# MARS_GPIO_MISC.net
KiCad netlist of a schematic drawn in Altium Designer
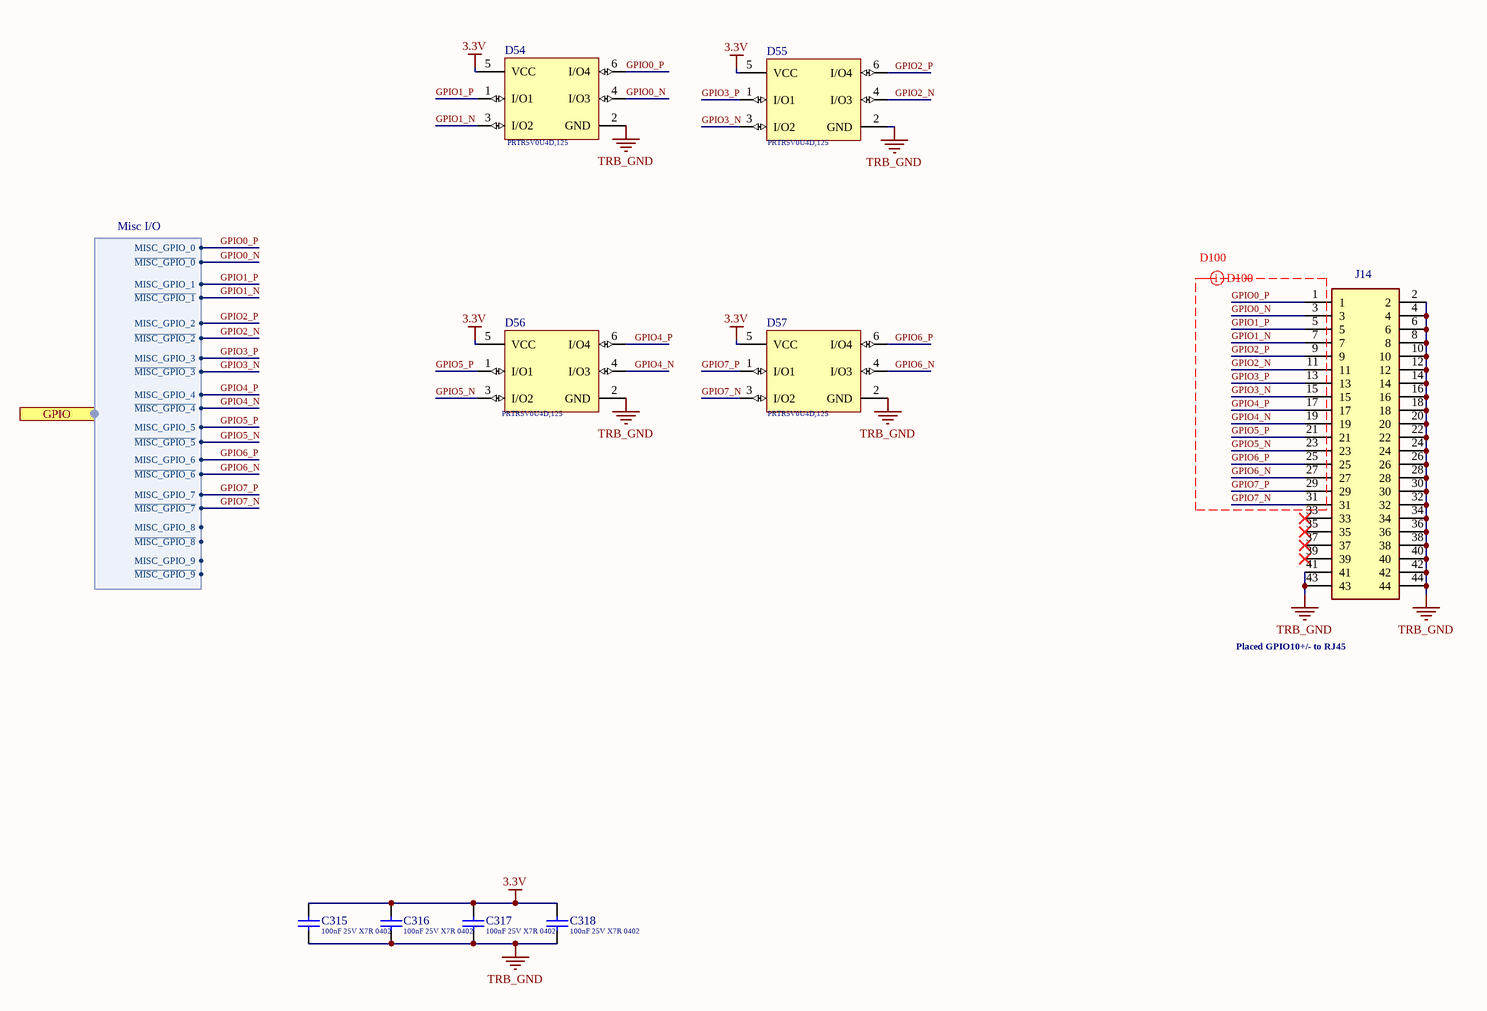
[diagram p0: MARS_GPIO_MISC.SchDoc]

(export (version "E")
  (design (tool "Eeschema 10.0.6"))
  (components
    (comp (ref "C315")
      (value "Cap_Taiyo_Yuden_TMK105B7104KV-FR_100nF")
      (footprint "Cap_Taiyo_Yuden_TMK105B7104KV-FR_100nF")
      (description "CAP CER 100nF 25V X7R 0402")
      (fields (field (name "CAPACITANCE") "100nF 25V X7R 0402"))
      (libsource (lib "Cap_Taiyo_Yuden_TMK105B7104KV-FR_100nF") (part "Cap_Taiyo_Yuden_TMK105B7104KV-FR_100nF"))
    )
    (comp (ref "C316")
      (value "Cap_Taiyo_Yuden_TMK105B7104KV-FR_100nF")
      (footprint "Cap_Taiyo_Yuden_TMK105B7104KV-FR_100nF")
      (description "CAP CER 100nF 25V X7R 0402")
      (fields (field (name "CAPACITANCE") "100nF 25V X7R 0402"))
      (libsource (lib "Cap_Taiyo_Yuden_TMK105B7104KV-FR_100nF") (part "Cap_Taiyo_Yuden_TMK105B7104KV-FR_100nF"))
    )
    (comp (ref "C317")
      (value "Cap_Taiyo_Yuden_TMK105B7104KV-FR_100nF")
      (footprint "Cap_Taiyo_Yuden_TMK105B7104KV-FR_100nF")
      (description "CAP CER 100nF 25V X7R 0402")
      (fields (field (name "CAPACITANCE") "100nF 25V X7R 0402"))
      (libsource (lib "Cap_Taiyo_Yuden_TMK105B7104KV-FR_100nF") (part "Cap_Taiyo_Yuden_TMK105B7104KV-FR_100nF"))
    )
    (comp (ref "C318")
      (value "Cap_Taiyo_Yuden_TMK105B7104KV-FR_100nF")
      (footprint "Cap_Taiyo_Yuden_TMK105B7104KV-FR_100nF")
      (description "CAP CER 100nF 25V X7R 0402")
      (fields (field (name "CAPACITANCE") "100nF 25V X7R 0402"))
      (libsource (lib "Cap_Taiyo_Yuden_TMK105B7104KV-FR_100nF") (part "Cap_Taiyo_Yuden_TMK105B7104KV-FR_100nF"))
    )
    (comp (ref "D54")
      (value "PRTR5V0U4D,125")
      (footprint "PRTR5V0U4D,125")
      (description "ESD Suppressors / TVS Diodes 5.5V QUAD R-R ESD ULTRA LOW CAP")
      (libsource (lib "PRTR5V0U4D,125") (part "PRTR5V0U4D,125"))
    )
    (comp (ref "D55")
      (value "PRTR5V0U4D,125")
      (footprint "PRTR5V0U4D,125")
      (description "ESD Suppressors / TVS Diodes 5.5V QUAD R-R ESD ULTRA LOW CAP")
      (libsource (lib "PRTR5V0U4D,125") (part "PRTR5V0U4D,125"))
    )
    (comp (ref "D56")
      (value "PRTR5V0U4D,125")
      (footprint "PRTR5V0U4D,125")
      (description "ESD Suppressors / TVS Diodes 5.5V QUAD R-R ESD ULTRA LOW CAP")
      (libsource (lib "PRTR5V0U4D,125") (part "PRTR5V0U4D,125"))
    )
    (comp (ref "D57")
      (value "PRTR5V0U4D,125")
      (footprint "PRTR5V0U4D,125")
      (description "ESD Suppressors / TVS Diodes 5.5V QUAD R-R ESD ULTRA LOW CAP")
      (libsource (lib "PRTR5V0U4D,125") (part "PRTR5V0U4D,125"))
    )
    (comp (ref "J14")
      (value "10-89-7442")
      (footprint "HDRV44W87P254_2X22_5601X508X864P")
      (description "Connector")
      (fields (field (name "MOUSER2 PART NUMBER") "538-10-89-7442"))
      (libsource (lib "Header_Molex_10-89-7442_44POS") (part "10-89-7442"))
    )
  )
  (nets
    (net (code "3") (name "/GPIO0_N") (class "Default")
      (node (ref "D54") (pin "4") (pinfunction "I/O3_4") (pintype "bidirectional"))
      (node (ref "J14") (pin "3") (pinfunction "3_3") (pintype "passive"))
    )
    (net (code "4") (name "/GPIO0_P") (class "Default")
      (node (ref "D54") (pin "6") (pinfunction "I/O4_6") (pintype "bidirectional"))
      (node (ref "J14") (pin "1") (pinfunction "1_1") (pintype "passive"))
    )
    (net (code "5") (name "/GPIO1_N") (class "Default")
      (node (ref "D54") (pin "3") (pinfunction "I/O2_3") (pintype "bidirectional"))
      (node (ref "J14") (pin "7") (pinfunction "7_7") (pintype "passive"))
    )
    (net (code "6") (name "/GPIO1_P") (class "Default")
      (node (ref "D54") (pin "1") (pinfunction "I/O1_1") (pintype "bidirectional"))
      (node (ref "J14") (pin "5") (pinfunction "5_5") (pintype "passive"))
    )
    (net (code "7") (name "/GPIO2_N") (class "Default")
      (node (ref "D55") (pin "4") (pinfunction "I/O3_4") (pintype "bidirectional"))
      (node (ref "J14") (pin "11") (pinfunction "11_11") (pintype "passive"))
    )
    (net (code "8") (name "/GPIO2_P") (class "Default")
      (node (ref "D55") (pin "6") (pinfunction "I/O4_6") (pintype "bidirectional"))
      (node (ref "J14") (pin "9") (pinfunction "9_9") (pintype "passive"))
    )
    (net (code "9") (name "/GPIO3_N") (class "Default")
      (node (ref "D55") (pin "3") (pinfunction "I/O2_3") (pintype "bidirectional"))
      (node (ref "J14") (pin "15") (pinfunction "15_15") (pintype "passive"))
    )
    (net (code "10") (name "/GPIO3_P") (class "Default")
      (node (ref "D55") (pin "1") (pinfunction "I/O1_1") (pintype "bidirectional"))
      (node (ref "J14") (pin "13") (pinfunction "13_13") (pintype "passive"))
    )
    (net (code "11") (name "/GPIO4_N") (class "Default")
      (node (ref "D56") (pin "4") (pinfunction "I/O3_4") (pintype "bidirectional"))
      (node (ref "J14") (pin "19") (pinfunction "19_19") (pintype "passive"))
    )
    (net (code "12") (name "/GPIO4_P") (class "Default")
      (node (ref "D56") (pin "6") (pinfunction "I/O4_6") (pintype "bidirectional"))
      (node (ref "J14") (pin "17") (pinfunction "17_17") (pintype "passive"))
    )
    (net (code "13") (name "/GPIO5_N") (class "Default")
      (node (ref "D56") (pin "3") (pinfunction "I/O2_3") (pintype "bidirectional"))
      (node (ref "J14") (pin "23") (pinfunction "23_23") (pintype "passive"))
    )
    (net (code "14") (name "/GPIO5_P") (class "Default")
      (node (ref "D56") (pin "1") (pinfunction "I/O1_1") (pintype "bidirectional"))
      (node (ref "J14") (pin "21") (pinfunction "21_21") (pintype "passive"))
    )
    (net (code "15") (name "/GPIO6_N") (class "Default")
      (node (ref "D57") (pin "4") (pinfunction "I/O3_4") (pintype "bidirectional"))
      (node (ref "J14") (pin "27") (pinfunction "27_27") (pintype "passive"))
    )
    (net (code "16") (name "/GPIO6_P") (class "Default")
      (node (ref "D57") (pin "6") (pinfunction "I/O4_6") (pintype "bidirectional"))
      (node (ref "J14") (pin "25") (pinfunction "25_25") (pintype "passive"))
    )
    (net (code "17") (name "/GPIO7_N") (class "Default")
      (node (ref "D57") (pin "3") (pinfunction "I/O2_3") (pintype "bidirectional"))
      (node (ref "J14") (pin "31") (pinfunction "31_31") (pintype "passive"))
    )
    (net (code "18") (name "/GPIO7_P") (class "Default")
      (node (ref "D57") (pin "1") (pinfunction "I/O1_1") (pintype "bidirectional"))
      (node (ref "J14") (pin "29") (pinfunction "29_29") (pintype "passive"))
    )
    (net (code "20") (name "3.3V") (class "Default")
      (node (ref "C315") (pin "2") (pinfunction "2_2") (pintype "passive"))
      (node (ref "C316") (pin "2") (pinfunction "2_2") (pintype "passive"))
      (node (ref "C317") (pin "2") (pinfunction "2_2") (pintype "passive"))
      (node (ref "C318") (pin "2") (pinfunction "2_2") (pintype "passive"))
      (node (ref "D54") (pin "5") (pinfunction "VCC_5") (pintype "power_in"))
      (node (ref "D55") (pin "5") (pinfunction "VCC_5") (pintype "power_in"))
      (node (ref "D56") (pin "5") (pinfunction "VCC_5") (pintype "power_in"))
      (node (ref "D57") (pin "5") (pinfunction "VCC_5") (pintype "power_in"))
    )
    (net (code "21") (name "TRB_GND") (class "Default")
      (node (ref "C315") (pin "1") (pinfunction "1_1") (pintype "passive"))
      (node (ref "C316") (pin "1") (pinfunction "1_1") (pintype "passive"))
      (node (ref "C317") (pin "1") (pinfunction "1_1") (pintype "passive"))
      (node (ref "C318") (pin "1") (pinfunction "1_1") (pintype "passive"))
      (node (ref "D54") (pin "2") (pinfunction "GND_2") (pintype "power_in"))
      (node (ref "D55") (pin "2") (pinfunction "GND_2") (pintype "power_in"))
      (node (ref "D56") (pin "2") (pinfunction "GND_2") (pintype "power_in"))
      (node (ref "D57") (pin "2") (pinfunction "GND_2") (pintype "power_in"))
      (node (ref "J14") (pin "10") (pinfunction "10_10") (pintype "passive"))
      (node (ref "J14") (pin "12") (pinfunction "12_12") (pintype "passive"))
      (node (ref "J14") (pin "14") (pinfunction "14_14") (pintype "passive"))
      (node (ref "J14") (pin "16") (pinfunction "16_16") (pintype "passive"))
      (node (ref "J14") (pin "18") (pinfunction "18_18") (pintype "passive"))
      (node (ref "J14") (pin "2") (pinfunction "2_2") (pintype "passive"))
      (node (ref "J14") (pin "20") (pinfunction "20_20") (pintype "passive"))
      (node (ref "J14") (pin "22") (pinfunction "22_22") (pintype "passive"))
      (node (ref "J14") (pin "24") (pinfunction "24_24") (pintype "passive"))
      (node (ref "J14") (pin "26") (pinfunction "26_26") (pintype "passive"))
      (node (ref "J14") (pin "28") (pinfunction "28_28") (pintype "passive"))
      (node (ref "J14") (pin "30") (pinfunction "30_30") (pintype "passive"))
      (node (ref "J14") (pin "32") (pinfunction "32_32") (pintype "passive"))
      (node (ref "J14") (pin "34") (pinfunction "34_34") (pintype "passive"))
      (node (ref "J14") (pin "36") (pinfunction "36_36") (pintype "passive"))
      (node (ref "J14") (pin "38") (pinfunction "38_38") (pintype "passive"))
      (node (ref "J14") (pin "4") (pinfunction "4_4") (pintype "passive"))
      (node (ref "J14") (pin "40") (pinfunction "40_40") (pintype "passive"))
      (node (ref "J14") (pin "41") (pinfunction "41_41") (pintype "passive"))
      (node (ref "J14") (pin "42") (pinfunction "42_42") (pintype "passive"))
      (node (ref "J14") (pin "43") (pinfunction "43_43") (pintype "passive"))
      (node (ref "J14") (pin "44") (pinfunction "44_44") (pintype "passive"))
      (node (ref "J14") (pin "6") (pinfunction "6_6") (pintype "passive"))
      (node (ref "J14") (pin "8") (pinfunction "8_8") (pintype "passive"))
    )
    (net (code "22") (name "unconnected-(J14-Pad33)") (class "Default")
      (node (ref "J14") (pin "33") (pinfunction "33_33") (pintype "passive+no_connect"))
    )
    (net (code "23") (name "unconnected-(J14-Pad35)") (class "Default")
      (node (ref "J14") (pin "35") (pinfunction "35_35") (pintype "passive+no_connect"))
    )
    (net (code "24") (name "unconnected-(J14-Pad37)") (class "Default")
      (node (ref "J14") (pin "37") (pinfunction "37_37") (pintype "passive+no_connect"))
    )
    (net (code "25") (name "unconnected-(J14-Pad39)") (class "Default")
      (node (ref "J14") (pin "39") (pinfunction "39_39") (pintype "passive+no_connect"))
    )
  )
)
